# schematic.net
KiCad netlist of a schematic drawn in EasyEDA
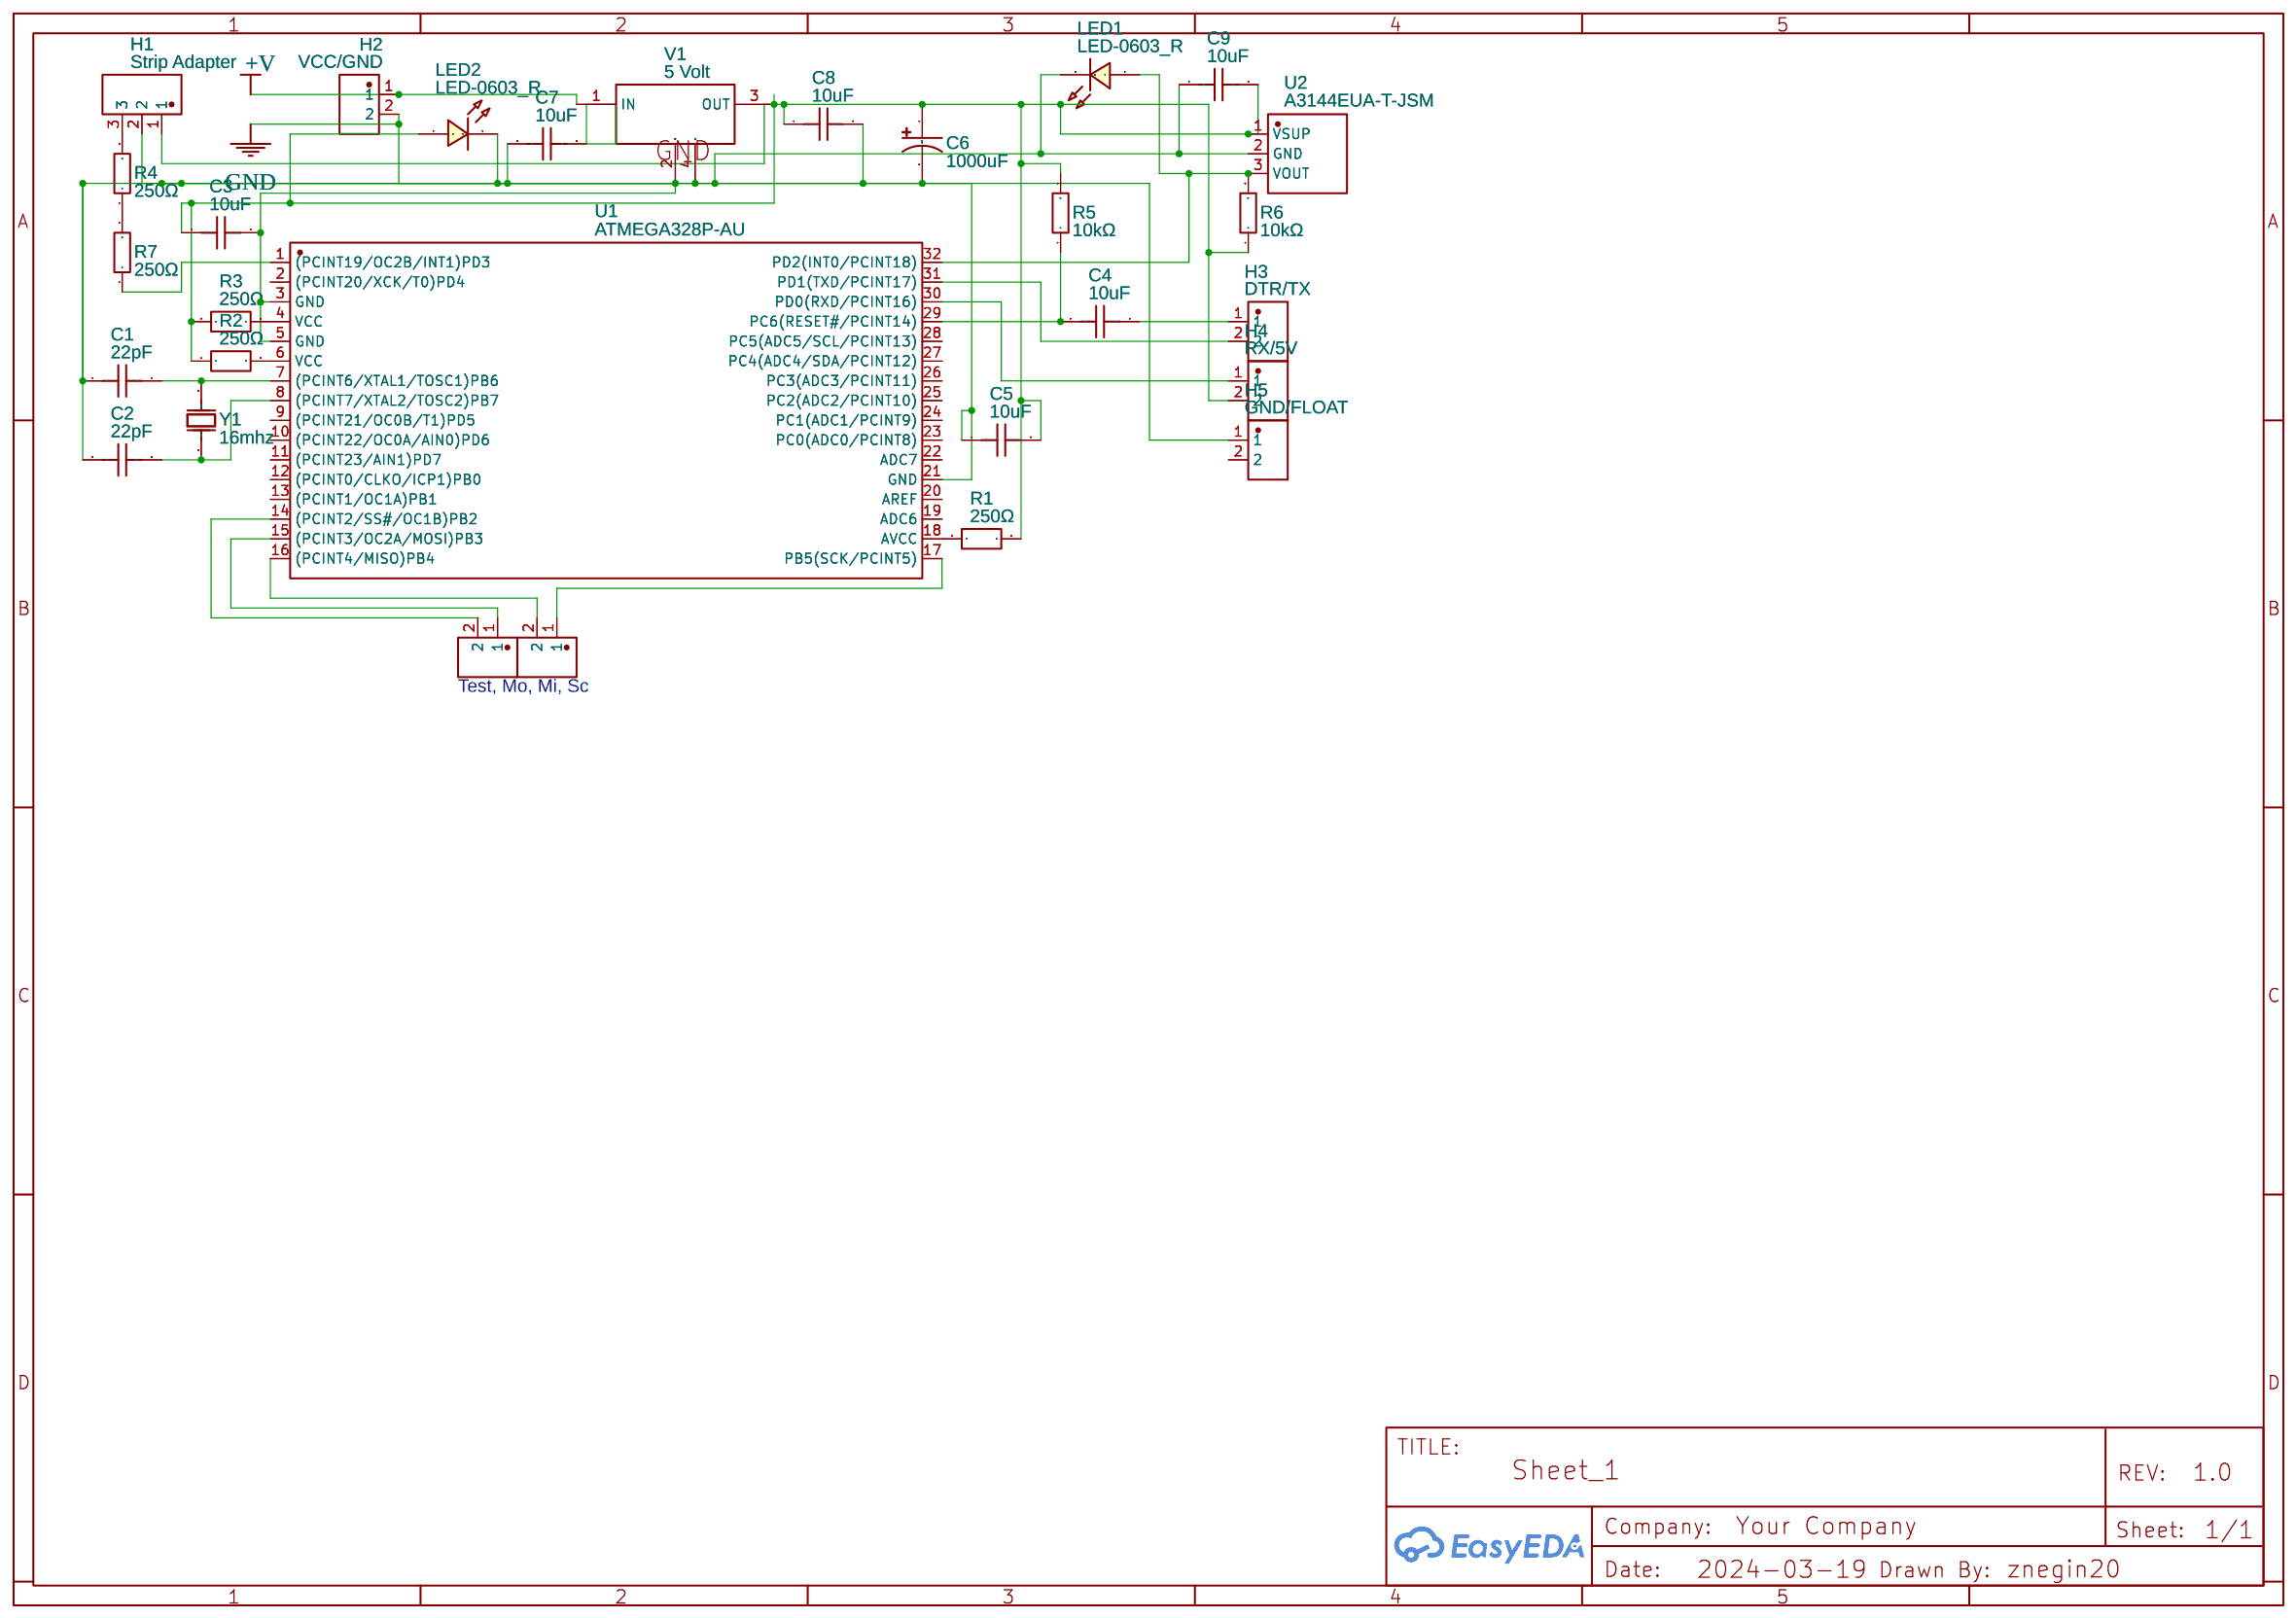
[diagram p0: schematic sheet]

(export (version "E")
  (design (tool "Eeschema 10.0.6"))
  (components
    (comp (ref "C1")
      (value "22pF")
      (fields
        (field (name "Manufacturer Part") "CL05C220JB5NNNC")
        (field (name "Manufacturer") "SAMSUNG(三星)")
      )
      (libsource (lib "") (part "CL05C220JB5NNNC"))
    )
    (comp (ref "C2")
      (value "22pF")
      (fields
        (field (name "Manufacturer Part") "CL05C220JB5NNNC")
        (field (name "Manufacturer") "SAMSUNG(三星)")
      )
      (libsource (lib "") (part "CL05C220JB5NNNC"))
    )
    (comp (ref "C3")
      (value "10uF")
      (fields
        (field (name "Manufacturer Part") "CL10A106MA8NRNC")
        (field (name "Manufacturer") "SAMSUNG(三星)")
      )
      (libsource (lib "") (part "CL10A106MA8NRNC"))
    )
    (comp (ref "C4")
      (value "10uF")
      (fields
        (field (name "Manufacturer Part") "CL10A106MA8NRNC")
        (field (name "Manufacturer") "SAMSUNG(三星)")
      )
      (libsource (lib "") (part "CL10A106MA8NRNC"))
    )
    (comp (ref "C5")
      (value "10uF")
      (fields
        (field (name "Manufacturer Part") "CL10A106MA8NRNC")
        (field (name "Manufacturer") "SAMSUNG(三星)")
      )
      (libsource (lib "") (part "CL10A106MA8NRNC"))
    )
    (comp (ref "C6")
      (value "1000uF")
      (fields (field (name "Manufacturer Part") "VT1C102M1010") (field (name "Manufacturer") "ROQANG(容强)"))
      (libsource (lib "") (part "VT1C102M1010"))
    )
    (comp (ref "C7")
      (value "10uF")
      (fields
        (field (name "Manufacturer Part") "CL10A106MA8NRNC")
        (field (name "Manufacturer") "SAMSUNG(三星)")
      )
      (libsource (lib "") (part "CL10A106MA8NRNC"))
    )
    (comp (ref "C8")
      (value "10uF")
      (fields
        (field (name "Manufacturer Part") "CL10A106MA8NRNC")
        (field (name "Manufacturer") "SAMSUNG(三星)")
      )
      (libsource (lib "") (part "CL10A106MA8NRNC"))
    )
    (comp (ref "C9")
      (value "10uF")
      (fields
        (field (name "Manufacturer Part") "CL10A106MA8NRNC")
        (field (name "Manufacturer") "SAMSUNG(三星)")
      )
      (libsource (lib "") (part "CL10A106MA8NRNC"))
    )
    (comp (ref "H1")
      (value "Strip Adapter")
      (fields (field (name "Manufacturer Part") "CS-1165SDIG-1*3") (field (name "Manufacturer") "CST(永丰盈)"))
      (libsource (lib "") (part "CS-1165SDIG-1*3"))
    )
    (comp (ref "H2")
      (value "VCC/GND")
      (fields
        (field (name "Manufacturer Part") "PM200-1-02-W-4.3")
        (field (name "Manufacturer") "HCTL(华灿天禄)")
      )
      (libsource (lib "") (part "PM200-1-02-W-4.3_2"))
    )
    (comp (ref "H3")
      (value "DTR/TX")
      (fields
        (field (name "Manufacturer Part") "PM200-1-02-W-4.3")
        (field (name "Manufacturer") "HCTL(华灿天禄)")
      )
      (libsource (lib "") (part "PM200-1-02-W-4.3"))
    )
    (comp (ref "H4")
      (value "RX/5V")
      (fields
        (field (name "Manufacturer Part") "PM200-1-02-W-4.3")
        (field (name "Manufacturer") "HCTL(华灿天禄)")
      )
      (libsource (lib "") (part "PM200-1-02-W-4.3"))
    )
    (comp (ref "H5")
      (value "GND/FLOAT")
      (fields
        (field (name "Manufacturer Part") "PM200-1-02-W-4.3")
        (field (name "Manufacturer") "HCTL(华灿天禄)")
      )
      (libsource (lib "") (part "PM200-1-02-W-4.3"))
    )
    (comp (ref "H7")
      (value "GND/FLOAT")
      (fields
        (field (name "Manufacturer Part") "PM200-1-02-W-4.3")
        (field (name "Manufacturer") "HCTL(华灿天禄)")
      )
      (libsource (lib "") (part "PM200-1-02-W-4.3_1"))
    )
    (comp (ref "H8")
      (value "GND/FLOAT")
      (fields
        (field (name "Manufacturer Part") "PM200-1-02-W-4.3")
        (field (name "Manufacturer") "HCTL(华灿天禄)")
      )
      (libsource (lib "") (part "PM200-1-02-W-4.3_1"))
    )
    (comp (ref "LED1")
      (value "LED-0603_R")
      (fields
        (field (name "Manufacturer Part") "19-217/R6C-AL1M2VY/3T")
        (field (name "Manufacturer") "EVERLIGHT(台湾亿光)")
      )
      (libsource (lib "") (part "LED-0603_R_1"))
    )
    (comp (ref "LED2")
      (value "LED-0603_R")
      (fields
        (field (name "Manufacturer Part") "19-217/R6C-AL1M2VY/3T")
        (field (name "Manufacturer") "EVERLIGHT(台湾亿光)")
      )
      (libsource (lib "") (part "LED-0603_R"))
    )
    (comp (ref "R1")
      (value "250Ω")
      (fields (field (name "Manufacturer Part") "ARG03DTC2500") (field (name "Manufacturer") "Viking(光颉)"))
      (libsource (lib "") (part "ARG03DTC2500"))
    )
    (comp (ref "R2")
      (value "250Ω")
      (fields (field (name "Manufacturer Part") "ARG03DTC2500") (field (name "Manufacturer") "Viking(光颉)"))
      (libsource (lib "") (part "ARG03DTC2500"))
    )
    (comp (ref "R3")
      (value "250Ω")
      (fields (field (name "Manufacturer Part") "ARG03DTC2500") (field (name "Manufacturer") "Viking(光颉)"))
      (libsource (lib "") (part "ARG03DTC2500"))
    )
    (comp (ref "R4")
      (value "250Ω")
      (fields (field (name "Manufacturer Part") "ARG02FTC4700") (field (name "Manufacturer") "Viking(光颉)"))
      (libsource (lib "") (part "ARG02FTC4700"))
    )
    (comp (ref "R5")
      (value "10kΩ")
      (fields (field (name "Manufacturer Part") "AR03BTDX1002") (field (name "Manufacturer") "Viking(光颉)"))
      (libsource (lib "") (part "AR03BTDX1002"))
    )
    (comp (ref "R6")
      (value "10kΩ")
      (fields (field (name "Manufacturer Part") "AR03BTDX1002") (field (name "Manufacturer") "Viking(光颉)"))
      (libsource (lib "") (part "AR03BTDX1002"))
    )
    (comp (ref "R7")
      (value "250Ω")
      (fields (field (name "Manufacturer Part") "ARG02FTC4700") (field (name "Manufacturer") "Viking(光颉)"))
      (libsource (lib "") (part "ARG02FTC4700"))
    )
    (comp (ref "U1")
      (value "ATMEGA328P-AU")
      (fields (field (name "Manufacturer") "MICROCHIP(美国微芯)"))
      (libsource (lib "") (part "ATMEGA328P-AU COPY"))
    )
    (comp (ref "U2")
      (value "A3144EUA-T-JSM")
      (fields (field (name "Manufacturer") "JSMSEMI(杰盛微)"))
      (libsource (lib "") (part "A3144EUA-T-JSM"))
    )
    (comp (ref "V1")
      (value "5 Volt")
      (fields (field (name "Manufacturer Part") "LM7805SX/NOPB") (field (name "Manufacturer") "TI(德州仪器)"))
      (libsource (lib "") (part "LM7805SX/NOPB"))
    )
    (comp (ref "Y1")
      (value "16mhz")
      (fields
        (field (name "Manufacturer Part") "HY16M49SSMDOB1R20")
        (field (name "Manufacturer") "Huiyuan crystal(惠源晶工)")
      )
      (libsource (lib "") (part "HY16M49SSMDOB1R20"))
    )
  )
  (nets
    (net (code "1") (name "+V") (class "Default")
      (node (ref "H2") (pin "1") (pinfunction "1_1") (pintype "unspecified"))
      (node (ref "V1") (pin "1") (pinfunction "IN_1") (pintype "passive"))
    )
    (net (code "2") (name "GND") (class "Default")
      (node (ref "C1") (pin "1") (pinfunction "1_1") (pintype "unspecified"))
      (node (ref "C2") (pin "1") (pinfunction "1_1") (pintype "unspecified"))
      (node (ref "C3") (pin "2") (pinfunction "2_2") (pintype "unspecified"))
      (node (ref "C5") (pin "1") (pinfunction "1_1") (pintype "unspecified"))
      (node (ref "C6") (pin "2") (pinfunction "2_2") (pintype "unspecified"))
      (node (ref "C7") (pin "1") (pinfunction "1_1") (pintype "unspecified"))
      (node (ref "C8") (pin "2") (pinfunction "2_2") (pintype "unspecified"))
      (node (ref "C9") (pin "1") (pinfunction "1_1") (pintype "unspecified"))
      (node (ref "H1") (pin "2") (pinfunction "2_2") (pintype "unspecified"))
      (node (ref "H2") (pin "2") (pinfunction "2_2") (pintype "unspecified"))
      (node (ref "H5") (pin "1") (pinfunction "1_1") (pintype "unspecified"))
      (node (ref "LED1") (pin "2") (pinfunction "2_2") (pintype "unspecified"))
      (node (ref "LED2") (pin "2") (pinfunction "2_2") (pintype "unspecified"))
      (node (ref "U1") (pin "21") (pinfunction "GND_21") (pintype "unspecified"))
      (node (ref "U1") (pin "3") (pinfunction "GND_3") (pintype "unspecified"))
      (node (ref "U1") (pin "5") (pinfunction "GND_5") (pintype "unspecified"))
      (node (ref "U2") (pin "2") (pinfunction "GND_2") (pintype "unspecified"))
      (node (ref "V1") (pin "2") (pinfunction "GND_2") (pintype "passive"))
      (node (ref "V1") (pin "4") (pinfunction "GND_4") (pintype "passive"))
    )
    (net (code "3") (name "Net-(C4-Pad2)") (class "Default")
      (node (ref "C4") (pin "2") (pinfunction "2_2") (pintype "unspecified"))
      (node (ref "H3") (pin "1") (pinfunction "1_1") (pintype "unspecified"))
    )
    (net (code "4") (name "Net-(H1-Pad3)") (class "Default")
      (node (ref "H1") (pin "3") (pinfunction "3_3") (pintype "unspecified"))
      (node (ref "R4") (pin "2") (pinfunction "2_2") (pintype "unspecified"))
    )
    (net (code "5") (name "Net-(R2-Pad2)") (class "Default")
      (node (ref "R2") (pin "2") (pinfunction "2_2") (pintype "unspecified"))
      (node (ref "U1") (pin "6") (pinfunction "VCC_6") (pintype "unspecified"))
    )
    (net (code "6") (name "Net-(R3-Pad2)") (class "Default")
      (node (ref "R3") (pin "2") (pinfunction "2_2") (pintype "unspecified"))
      (node (ref "U1") (pin "4") (pinfunction "VCC_4") (pintype "unspecified"))
    )
    (net (code "7") (name "Net-(R4-Pad1)") (class "Default")
      (node (ref "R4") (pin "1") (pinfunction "1_1") (pintype "unspecified"))
      (node (ref "R7") (pin "2") (pinfunction "2_2") (pintype "unspecified"))
    )
    (net (code "8") (name "Net-(U1-(PCINT2{slash}SS#{slash}OC1B)PB2)") (class "Default")
      (node (ref "H8") (pin "2") (pinfunction "2_2") (pintype "unspecified"))
      (node (ref "U1") (pin "14") (pinfunction "(PCINT2/SS#/OC1B)PB2_14") (pintype "unspecified"))
    )
    (net (code "9") (name "Net-(U1-(PCINT3{slash}OC2A{slash}MOSI)PB3)") (class "Default")
      (node (ref "H8") (pin "1") (pinfunction "1_1") (pintype "unspecified"))
      (node (ref "U1") (pin "15") (pinfunction "(PCINT3/OC2A/MOSI)PB3_15") (pintype "unspecified"))
    )
    (net (code "10") (name "Net-(U1-(PCINT4{slash}MISO)PB4)") (class "Default")
      (node (ref "H7") (pin "2") (pinfunction "2_2") (pintype "unspecified"))
      (node (ref "U1") (pin "16") (pinfunction "(PCINT4/MISO)PB4_16") (pintype "unspecified"))
    )
    (net (code "11") (name "Net-(U1-(PCINT6{slash}XTAL1{slash}TOSC1)PB6)") (class "Default")
      (node (ref "C1") (pin "2") (pinfunction "2_2") (pintype "unspecified"))
      (node (ref "U1") (pin "7") (pinfunction "(PCINT6/XTAL1/TOSC1)PB6_7") (pintype "unspecified"))
      (node (ref "Y1") (pin "2") (pinfunction "OSC2_2") (pintype "input"))
    )
    (net (code "12") (name "Net-(U1-(PCINT7{slash}XTAL2{slash}TOSC2)PB7)") (class "Default")
      (node (ref "C2") (pin "2") (pinfunction "2_2") (pintype "unspecified"))
      (node (ref "U1") (pin "8") (pinfunction "(PCINT7/XTAL2/TOSC2)PB7_8") (pintype "unspecified"))
      (node (ref "Y1") (pin "1") (pinfunction "OSC1_1") (pintype "input"))
    )
    (net (code "13") (name "Net-(U1-(PCINT19{slash}OC2B{slash}INT1)PD3)") (class "Default")
      (node (ref "R7") (pin "1") (pinfunction "1_1") (pintype "unspecified"))
      (node (ref "U1") (pin "1") (pinfunction "(PCINT19/OC2B/INT1)PD3_1") (pintype "unspecified"))
    )
    (net (code "14") (name "Net-(U1-AVCC)") (class "Default")
      (node (ref "R1") (pin "1") (pinfunction "1_1") (pintype "unspecified"))
      (node (ref "U1") (pin "18") (pinfunction "AVCC_18") (pintype "unspecified"))
    )
    (net (code "15") (name "Net-(U1-PB5(SCK{slash}PCINT5))") (class "Default")
      (node (ref "H7") (pin "1") (pinfunction "1_1") (pintype "unspecified"))
      (node (ref "U1") (pin "17") (pinfunction "PB5(SCK/PCINT5)_17") (pintype "unspecified"))
    )
    (net (code "16") (name "Net-(U1-PC6(RESET#{slash}PCINT14))") (class "Default")
      (node (ref "C4") (pin "1") (pinfunction "1_1") (pintype "unspecified"))
      (node (ref "R5") (pin "1") (pinfunction "1_1") (pintype "unspecified"))
      (node (ref "U1") (pin "29") (pinfunction "PC6(RESET#/PCINT14)_29") (pintype "unspecified"))
    )
    (net (code "17") (name "Net-(U1-PD0(RXD{slash}PCINT16))") (class "Default")
      (node (ref "H4") (pin "1") (pinfunction "1_1") (pintype "unspecified"))
      (node (ref "U1") (pin "30") (pinfunction "PD0(RXD/PCINT16)_30") (pintype "unspecified"))
    )
    (net (code "18") (name "Net-(U1-PD1(TXD{slash}PCINT17))") (class "Default")
      (node (ref "H3") (pin "2") (pinfunction "2_2") (pintype "unspecified"))
      (node (ref "U1") (pin "31") (pinfunction "PD1(TXD/PCINT17)_31") (pintype "unspecified"))
    )
    (net (code "19") (name "Net-(U1-PD2(INT0{slash}PCINT18))") (class "Default")
      (node (ref "LED1") (pin "1") (pinfunction "1_1") (pintype "unspecified"))
      (node (ref "R6") (pin "2") (pinfunction "2_2") (pintype "unspecified"))
      (node (ref "U1") (pin "32") (pinfunction "PD2(INT0/PCINT18)_32") (pintype "unspecified"))
      (node (ref "U2") (pin "3") (pinfunction "VOUT_3") (pintype "unspecified"))
    )
    (net (code "20") (name "Net-(U2-VSUP)") (class "Default")
      (node (ref "C3") (pin "1") (pinfunction "1_1") (pintype "unspecified"))
      (node (ref "C5") (pin "2") (pinfunction "2_2") (pintype "unspecified"))
      (node (ref "C6") (pin "1") (pinfunction "1_1") (pintype "unspecified"))
      (node (ref "C8") (pin "1") (pinfunction "1_1") (pintype "unspecified"))
      (node (ref "C9") (pin "2") (pinfunction "2_2") (pintype "unspecified"))
      (node (ref "H1") (pin "1") (pinfunction "1_1") (pintype "unspecified"))
      (node (ref "H4") (pin "2") (pinfunction "2_2") (pintype "unspecified"))
      (node (ref "LED2") (pin "1") (pinfunction "1_1") (pintype "unspecified"))
      (node (ref "R1") (pin "2") (pinfunction "2_2") (pintype "unspecified"))
      (node (ref "R2") (pin "1") (pinfunction "1_1") (pintype "unspecified"))
      (node (ref "R3") (pin "1") (pinfunction "1_1") (pintype "unspecified"))
      (node (ref "R5") (pin "2") (pinfunction "2_2") (pintype "unspecified"))
      (node (ref "R6") (pin "1") (pinfunction "1_1") (pintype "unspecified"))
      (node (ref "U2") (pin "1") (pinfunction "VSUP_1") (pintype "unspecified"))
      (node (ref "V1") (pin "3") (pinfunction "OUT_3") (pintype "passive"))
    )
    (net (code "21") (name "unconnected-(C7-Pad2)") (class "Default")
      (node (ref "C7") (pin "2") (pinfunction "2_2") (pintype "unspecified"))
    )
    (net (code "22") (name "unconnected-(H5-Pad2)") (class "Default")
      (node (ref "H5") (pin "2") (pinfunction "2_2") (pintype "unspecified"))
    )
    (net (code "23") (name "unconnected-(U1-(PCINT0{slash}CLKO{slash}ICP1)PB0-Pad12)") (class "Default")
      (node (ref "U1") (pin "12") (pinfunction "(PCINT0/CLKO/ICP1)PB0_12") (pintype "unspecified"))
    )
    (net (code "24") (name "unconnected-(U1-(PCINT1{slash}OC1A)PB1-Pad13)") (class "Default")
      (node (ref "U1") (pin "13") (pinfunction "(PCINT1/OC1A)PB1_13") (pintype "unspecified"))
    )
    (net (code "25") (name "unconnected-(U1-(PCINT20{slash}XCK{slash}T0)PD4-Pad2)") (class "Default")
      (node (ref "U1") (pin "2") (pinfunction "(PCINT20/XCK/T0)PD4_2") (pintype "unspecified"))
    )
    (net (code "26") (name "unconnected-(U1-(PCINT21{slash}OC0B{slash}T1)PD5-Pad9)") (class "Default")
      (node (ref "U1") (pin "9") (pinfunction "(PCINT21/OC0B/T1)PD5_9") (pintype "unspecified"))
    )
    (net (code "27") (name "unconnected-(U1-(PCINT22{slash}OC0A{slash}AIN0)PD6-Pad10)") (class "Default")
      (node (ref "U1") (pin "10") (pinfunction "(PCINT22/OC0A/AIN0)PD6_10") (pintype "unspecified"))
    )
    (net (code "28") (name "unconnected-(U1-(PCINT23{slash}AIN1)PD7-Pad11)") (class "Default")
      (node (ref "U1") (pin "11") (pinfunction "(PCINT23/AIN1)PD7_11") (pintype "unspecified"))
    )
    (net (code "29") (name "unconnected-(U1-ADC6-Pad19)") (class "Default")
      (node (ref "U1") (pin "19") (pinfunction "ADC6_19") (pintype "unspecified"))
    )
    (net (code "30") (name "unconnected-(U1-ADC7-Pad22)") (class "Default")
      (node (ref "U1") (pin "22") (pinfunction "ADC7_22") (pintype "unspecified"))
    )
    (net (code "31") (name "unconnected-(U1-AREF-Pad20)") (class "Default")
      (node (ref "U1") (pin "20") (pinfunction "AREF_20") (pintype "unspecified"))
    )
    (net (code "32") (name "unconnected-(U1-PC0(ADC0{slash}PCINT8)-Pad23)") (class "Default")
      (node (ref "U1") (pin "23") (pinfunction "PC0(ADC0/PCINT8)_23") (pintype "unspecified"))
    )
    (net (code "33") (name "unconnected-(U1-PC1(ADC1{slash}PCINT9)-Pad24)") (class "Default")
      (node (ref "U1") (pin "24") (pinfunction "PC1(ADC1/PCINT9)_24") (pintype "unspecified"))
    )
    (net (code "34") (name "unconnected-(U1-PC2(ADC2{slash}PCINT10)-Pad25)") (class "Default")
      (node (ref "U1") (pin "25") (pinfunction "PC2(ADC2/PCINT10)_25") (pintype "unspecified"))
    )
    (net (code "35") (name "unconnected-(U1-PC3(ADC3{slash}PCINT11)-Pad26)") (class "Default")
      (node (ref "U1") (pin "26") (pinfunction "PC3(ADC3/PCINT11)_26") (pintype "unspecified"))
    )
    (net (code "36") (name "unconnected-(U1-PC4(ADC4{slash}SDA{slash}PCINT12)-Pad27)") (class "Default")
      (node (ref "U1") (pin "27") (pinfunction "PC4(ADC4/SDA/PCINT12)_27") (pintype "unspecified"))
    )
    (net (code "37") (name "unconnected-(U1-PC5(ADC5{slash}SCL{slash}PCINT13)-Pad28)") (class "Default")
      (node (ref "U1") (pin "28") (pinfunction "PC5(ADC5/SCL/PCINT13)_28") (pintype "unspecified"))
    )
  )
)
